# DC_TO_DC.net
KiCad netlist of a schematic drawn in Altium Designer
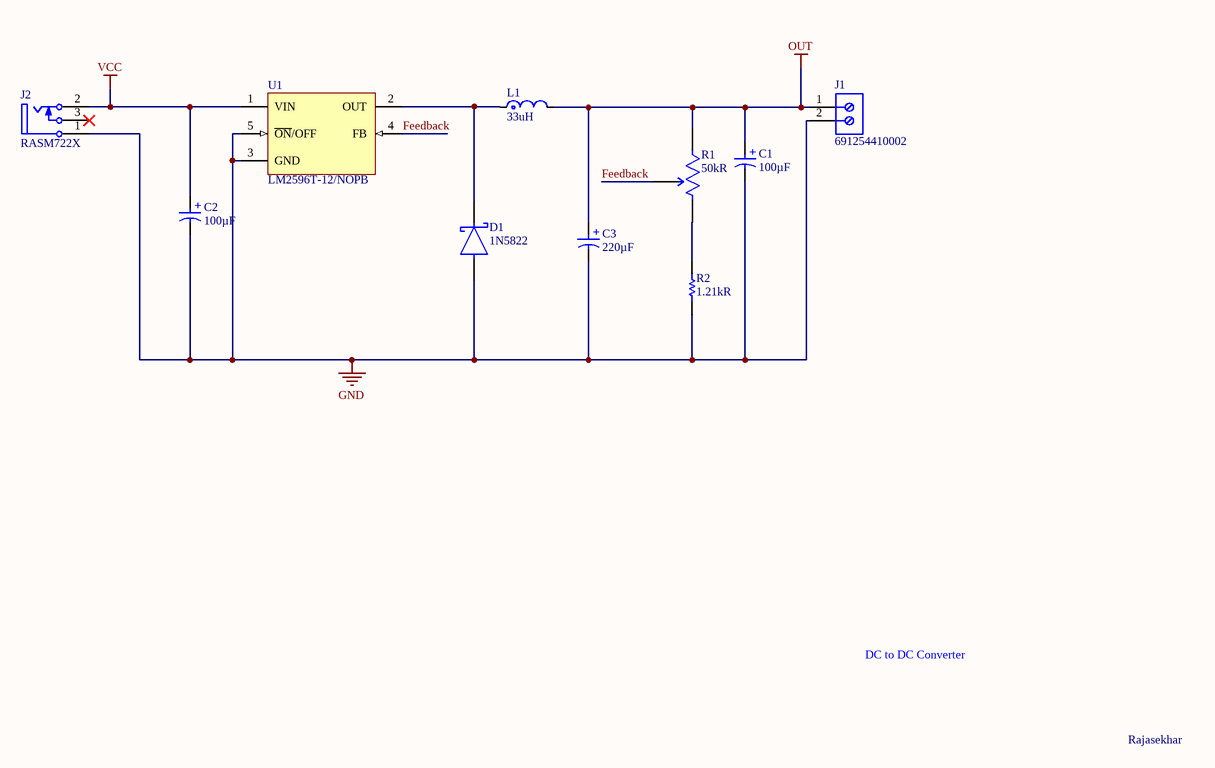
[diagram p0: DC TO DC.SchDoc]

(export (version "E")
  (design (tool "Eeschema 10.0.6"))
  (components
    (comp (ref "C1")
      (value "860130878011")
      (footprint "WCAP-ATET_D13H25")
      (description "860130878011 WCAP-ATET Aluminum Electrolytic Capacitors")
      (fields (field (name "CAPACITANCE") "100µF") (field (name "TOLERANCE") "20%"))
      (libsource (lib "Altium Content Vault") (part "Capacitor_Polarized"))
    )
    (comp (ref "C2")
      (value "860130878011")
      (footprint "WCAP-ATET_D13H25")
      (description "860130878011 WCAP-ATET Aluminum Electrolytic Capacitors")
      (fields (field (name "CAPACITANCE") "100µF") (field (name "TOLERANCE") "20%"))
      (libsource (lib "Altium Content Vault") (part "Capacitor_Polarized"))
    )
    (comp (ref "C3")
      (value "860160374017")
      (footprint "WCAP-ATLL_D8H11.5")
      (description "860160374017 Aluminium Electrolytic Capacitor-Leaded Rohs Compliant: Yes")
      (fields (field (name "CAPACITANCE") "220µF"))
      (libsource (lib "Altium Content Vault") (part "Capacitor_Polarized"))
    )
    (comp (ref "D1")
      (value "1N5822")
      (footprint "FP-DO-201AD-MFG")
      (description "DIODE SCHOTTKY 40V 3A DO201AD")
      (fields
        (field (name "OCTOPART") "https://octopart.com/1n5822-stmicroelectronics-323225")
        (field (name "MANUFACTURER") "STMicroelectronics")
      )
      (libsource (lib "Altium Content Vault") (part "1d6ec82d83fb6aee721767c19dac4b9"))
    )
    (comp (ref "J1")
      (value "691254410002")
      (footprint "691254410002")
      (libsource (lib "Altium Content Vault") (part "TBL - 1R - 02P - Screw"))
    )
    (comp (ref "J2")
      (value "RASM722X")
      (footprint "SWIT-RASM722X_V")
      (description "Power Jack, 5 A, 250 V, 3-Pin SMD, RoHS, Bulk")
      (fields (field (name "MANUFACTURER") "Switchcraft"))
      (libsource (lib "Rajasekharmuthukuru") (part "JACK-2CD3-TN"))
    )
    (comp (ref "L1")
      (value "B1047AS-330M=P3")
      (footprint "FP-DS75LC-MFG")
      (description "Shielded Wirewound Inductor 33uH 20% 1500mA 0.17Ω SMD")
      (fields (field (name "TOLERANCE") "20%") (field (name "INDUCTANCE") "33uH"))
      (libsource (lib "Altium Content Vault") (part "4cc4b267dca4c8e51f7102f422741d8"))
    )
    (comp (ref "R1")
      (value "3362P-1-503TLF")
      (footprint "FP-3362P-1-503TLF-MFG")
      (description "TRIMMER 50K OHM 0.5W PC PIN TOP")
      (fields (field (name "RESISTANCE") "50kR") (field (name "TOLERANCE") "10%"))
      (libsource (lib "Altium Content Vault") (part "2dcfd2547301a7d3209a5e99acfd772"))
    )
    (comp (ref "R2")
      (value "1.21kR")
      (footprint "RESC1608X55X25LL10T15")
      (fields (field (name "MANUFACTURER") "Yageo") (field (name "PART NUMBER") "RC0603FR-071K21L"))
      (libsource (lib "Altium Content Vault") (part "RES"))
    )
    (comp (ref "U1")
      (value "LM2596T-12/NOPB")
      (footprint "NDH0005A")
      (description "SIMPLE SWITCHER® Power Converter 150 KHz 3A Step-Down Voltage Regulator, 5-pin TO-220, Pb-Free")
      (fields (field (name "MANUFACTURER") "Texas Instruments"))
      (libsource (lib "Altium Content Vault") (part "PM-REG-LM2575HVT-12"))
    )
  )
  (nets
    (net (code "1") (name "/Feedback") (class "Default")
      (node (ref "R1") (pin "2") (pinfunction "WIPER_2") (pintype "passive"))
      (node (ref "U1") (pin "4") (pinfunction "FB_4") (pintype "input"))
    )
    (net (code "2") (name "GND") (class "Default")
      (node (ref "C1") (pin "2") (pinfunction "N_2") (pintype "passive"))
      (node (ref "C2") (pin "2") (pinfunction "N_2") (pintype "passive"))
      (node (ref "C3") (pin "2") (pinfunction "N_2") (pintype "passive"))
      (node (ref "D1") (pin "2") (pinfunction "A_2") (pintype "passive"))
      (node (ref "J1") (pin "2") (pinfunction "2_2") (pintype "passive"))
      (node (ref "J2") (pin "1") (pinfunction "SLEEVE_1") (pintype "passive"))
      (node (ref "R2") (pin "1") (pinfunction "1_1") (pintype "passive"))
      (node (ref "U1") (pin "3") (pinfunction "GND_3") (pintype "power_in"))
      (node (ref "U1") (pin "5") (pinfunction "~{ON}/OFF_5") (pintype "input"))
    )
    (net (code "3") (name "Net-(D1-C)") (class "Default")
      (node (ref "D1") (pin "1") (pinfunction "C_1") (pintype "passive"))
      (node (ref "L1") (pin "1") (pinfunction "1_1") (pintype "passive"))
      (node (ref "U1") (pin "2") (pinfunction "OUT_2") (pintype "power_in"))
    )
    (net (code "4") (name "Net-(R1-CW)") (class "Default")
      (node (ref "R1") (pin "3") (pinfunction "CW_3") (pintype "passive"))
      (node (ref "R2") (pin "2") (pinfunction "2_2") (pintype "passive"))
    )
    (net (code "5") (name "OUT") (class "Default")
      (node (ref "C1") (pin "1") (pinfunction "P_1") (pintype "passive"))
      (node (ref "C3") (pin "1") (pinfunction "P_1") (pintype "passive"))
      (node (ref "J1") (pin "1") (pinfunction "1_1") (pintype "passive"))
      (node (ref "L1") (pin "2") (pinfunction "2_2") (pintype "passive"))
      (node (ref "R1") (pin "1") (pinfunction "CCW_1") (pintype "passive"))
    )
    (net (code "6") (name "VCC") (class "Default")
      (node (ref "C2") (pin "1") (pinfunction "P_1") (pintype "passive"))
      (node (ref "J2") (pin "2") (pinfunction "TIP_2") (pintype "passive"))
      (node (ref "U1") (pin "1") (pinfunction "VIN_1") (pintype "power_in"))
    )
    (net (code "7") (name "unconnected-(J2-SHUNT-Pad3)") (class "Default")
      (node (ref "J2") (pin "3") (pinfunction "SHUNT_3") (pintype "passive+no_connect"))
    )
  )
)
